# 3501.net
KiCad netlist of a schematic drawn in Altium Designer
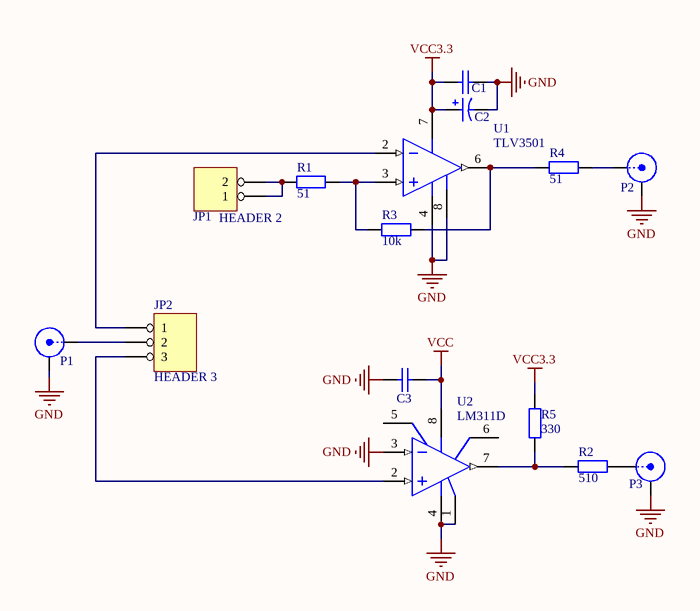
[diagram p0: 3501.SchDoc]

(export (version "E")
  (design (tool "Eeschema 10.0.6"))
  (components
    (comp (ref "C1")
      (value "Cap")
      (footprint "0805C")
      (description "Capacitor")
      (fields (field (name "PUBLISHER") "*"))
      (libsource (lib "我的终极元件库A") (part "Cap"))
    )
    (comp (ref "C2")
      (value "EC")
      (footprint "1206")
      (description "Bi-Polar Capacitor")
      (libsource (lib "我的终极元件库A") (part "Cap2"))
    )
    (comp (ref "C3")
      (value "Cap")
      (footprint "0805C")
      (description "Capacitor")
      (fields (field (name "PUBLISHER") "*"))
      (libsource (lib "我的终极元件库A") (part "Cap"))
    )
    (comp (ref "JP1") (value "HEADER 2") (footprint "header2") (libsource (lib "我的终极元件库A") (part "HEADER 2")))
    (comp (ref "JP2") (value "HEADER 3") (footprint "header3") (libsource (lib "我的终极元件库A") (part "HEADER 3")))
    (comp (ref "P1")
      (value "SMB")
      (footprint "SMB_V-RJ45")
      (description "SMB Straight Connector")
      (fields (field (name "PUBLISHER") "Altium Limited"))
      (libsource (lib "我的终极元件库A") (part "SMB"))
    )
    (comp (ref "P2")
      (value "SMB")
      (footprint "SMB_V-RJ45")
      (description "SMB Straight Connector")
      (fields (field (name "PUBLISHER") "Altium Limited"))
      (libsource (lib "我的终极元件库A") (part "SMB"))
    )
    (comp (ref "P3")
      (value "SMB")
      (footprint "SMB_V-RJ45")
      (description "SMB Straight Connector")
      (fields (field (name "PUBLISHER") "Altium Limited"))
      (libsource (lib "我的终极元件库A") (part "SMB"))
    )
    (comp (ref "R1")
      (value "51")
      (footprint "R-0603")
      (description "Resistor")
      (fields (field (name "Comment") "Res2") (field (name "PUBLISHER") "Altium Limited"))
      (libsource (lib "我的终极元件库A") (part "Res"))
    )
    (comp (ref "R2")
      (value "510")
      (footprint "R-0603")
      (description "Resistor")
      (fields (field (name "Comment") "Res2") (field (name "PUBLISHER") "Altium Limited"))
      (libsource (lib "我的终极元件库A") (part "Res"))
    )
    (comp (ref "R3")
      (value "10k")
      (footprint "R-0603")
      (description "Resistor")
      (fields (field (name "Comment") "Res2") (field (name "PUBLISHER") "Altium Limited"))
      (libsource (lib "我的终极元件库A") (part "Res"))
    )
    (comp (ref "R4")
      (value "51")
      (footprint "R-0603")
      (description "Resistor")
      (fields (field (name "Comment") "Res2") (field (name "PUBLISHER") "Altium Limited"))
      (libsource (lib "我的终极元件库A") (part "Res"))
    )
    (comp (ref "R5")
      (value "330")
      (footprint "0805R")
      (description "Resistor")
      (fields (field (name "Comment") "Res2") (field (name "PUBLISHER") "Altium Limited"))
      (libsource (lib "我的终极元件库A") (part "Res"))
    )
    (comp (ref "U1") (value "TLV3501") (footprint "D8") (libsource (lib "我的终极元件库A") (part "TLV3501")))
    (comp (ref "U2")
      (value "LM311D")
      (footprint "DIP8")
      (description "High-Performance Voltage Comparator")
      (fields (field (name "PUBLISHER") "Altium Limited"))
      (libsource (lib "我的终极元件库A") (part "LM311D"))
    )
  )
  (nets
    (net (code "1") (name "GND") (class "Default")
      (node (ref "C1") (pin "2") (pinfunction "2_2") (pintype "passive"))
      (node (ref "C2") (pin "2") (pinfunction "2_2") (pintype "passive"))
      (node (ref "C3") (pin "1") (pinfunction "1_1") (pintype "passive"))
      (node (ref "P1") (pin "2") (pinfunction "Y_2") (pintype "passive"))
      (node (ref "P2") (pin "2") (pinfunction "Y_2") (pintype "passive"))
      (node (ref "P3") (pin "2") (pinfunction "Y_2") (pintype "passive"))
      (node (ref "U1") (pin "4") (pinfunction "V-_4") (pintype "power_in"))
      (node (ref "U1") (pin "8") (pinfunction "~{DI}S_8") (pintype "power_in"))
      (node (ref "U2") (pin "1") (pinfunction "GND_1") (pintype "power_in"))
      (node (ref "U2") (pin "3") (pinfunction "IN-_3") (pintype "input"))
      (node (ref "U2") (pin "4") (pinfunction "V-_4") (pintype "power_in"))
    )
    (net (code "2") (name "Net-(JP1-Pad1)") (class "Default")
      (node (ref "JP1") (pin "1") (pinfunction "1_1") (pintype "passive"))
      (node (ref "JP1") (pin "2") (pinfunction "2_2") (pintype "passive"))
      (node (ref "R1") (pin "1") (pinfunction "1_1") (pintype "passive"))
    )
    (net (code "3") (name "Net-(P1-X)") (class "Default")
      (node (ref "JP2") (pin "2") (pinfunction "2_2") (pintype "passive"))
      (node (ref "P1") (pin "1") (pinfunction "X_1") (pintype "passive"))
    )
    (net (code "4") (name "Net-(P2-X)") (class "Default")
      (node (ref "P2") (pin "1") (pinfunction "X_1") (pintype "passive"))
      (node (ref "R4") (pin "2") (pinfunction "2_2") (pintype "passive"))
    )
    (net (code "5") (name "Net-(P3-X)") (class "Default")
      (node (ref "P3") (pin "1") (pinfunction "X_1") (pintype "passive"))
      (node (ref "R2") (pin "2") (pinfunction "2_2") (pintype "passive"))
    )
    (net (code "6") (name "Net-(U1-IN+)") (class "Default")
      (node (ref "R1") (pin "2") (pinfunction "2_2") (pintype "passive"))
      (node (ref "R3") (pin "1") (pinfunction "1_1") (pintype "passive"))
      (node (ref "U1") (pin "3") (pinfunction "IN+_3") (pintype "input"))
    )
    (net (code "7") (name "Net-(U1-IN-)") (class "Default")
      (node (ref "JP2") (pin "1") (pinfunction "1_1") (pintype "passive"))
      (node (ref "U1") (pin "2") (pinfunction "IN-_2") (pintype "input"))
    )
    (net (code "8") (name "Net-(U1-OUT)") (class "Default")
      (node (ref "R3") (pin "2") (pinfunction "2_2") (pintype "passive"))
      (node (ref "R4") (pin "1") (pinfunction "1_1") (pintype "passive"))
      (node (ref "U1") (pin "6") (pinfunction "OUT_6") (pintype "output"))
    )
    (net (code "9") (name "Net-(U2-IN+)") (class "Default")
      (node (ref "JP2") (pin "3") (pinfunction "3_3") (pintype "passive"))
      (node (ref "U2") (pin "2") (pinfunction "IN+_2") (pintype "input"))
    )
    (net (code "10") (name "Net-(U2-OUT)") (class "Default")
      (node (ref "R2") (pin "1") (pinfunction "1_1") (pintype "passive"))
      (node (ref "R5") (pin "1") (pinfunction "1_1") (pintype "passive"))
      (node (ref "U2") (pin "7") (pinfunction "OUT_7") (pintype "output"))
    )
    (net (code "11") (name "VCC") (class "Default")
      (node (ref "C3") (pin "2") (pinfunction "2_2") (pintype "passive"))
      (node (ref "U2") (pin "8") (pinfunction "V+_8") (pintype "power_in"))
    )
    (net (code "12") (name "VCC3.3") (class "Default")
      (node (ref "C1") (pin "1") (pinfunction "1_1") (pintype "passive"))
      (node (ref "C2") (pin "1") (pinfunction "1_1") (pintype "passive"))
      (node (ref "R5") (pin "2") (pinfunction "2_2") (pintype "passive"))
      (node (ref "U1") (pin "7") (pinfunction "V+_7") (pintype "power_in"))
    )
    (net (code "13") (name "unconnected-(U2-BAL-Pad5)") (class "Default")
      (node (ref "U2") (pin "5") (pinfunction "BAL_5") (pintype "passive"))
    )
    (net (code "14") (name "unconnected-(U2-BAL{slash}STB-Pad6)") (class "Default")
      (node (ref "U2") (pin "6") (pinfunction "BAL/STB_6") (pintype "passive"))
    )
  )
)
